# ESP32_ublox_IMU_2020-12-27_17-32-34.net
KiCad netlist of a schematic drawn in Altium Designer
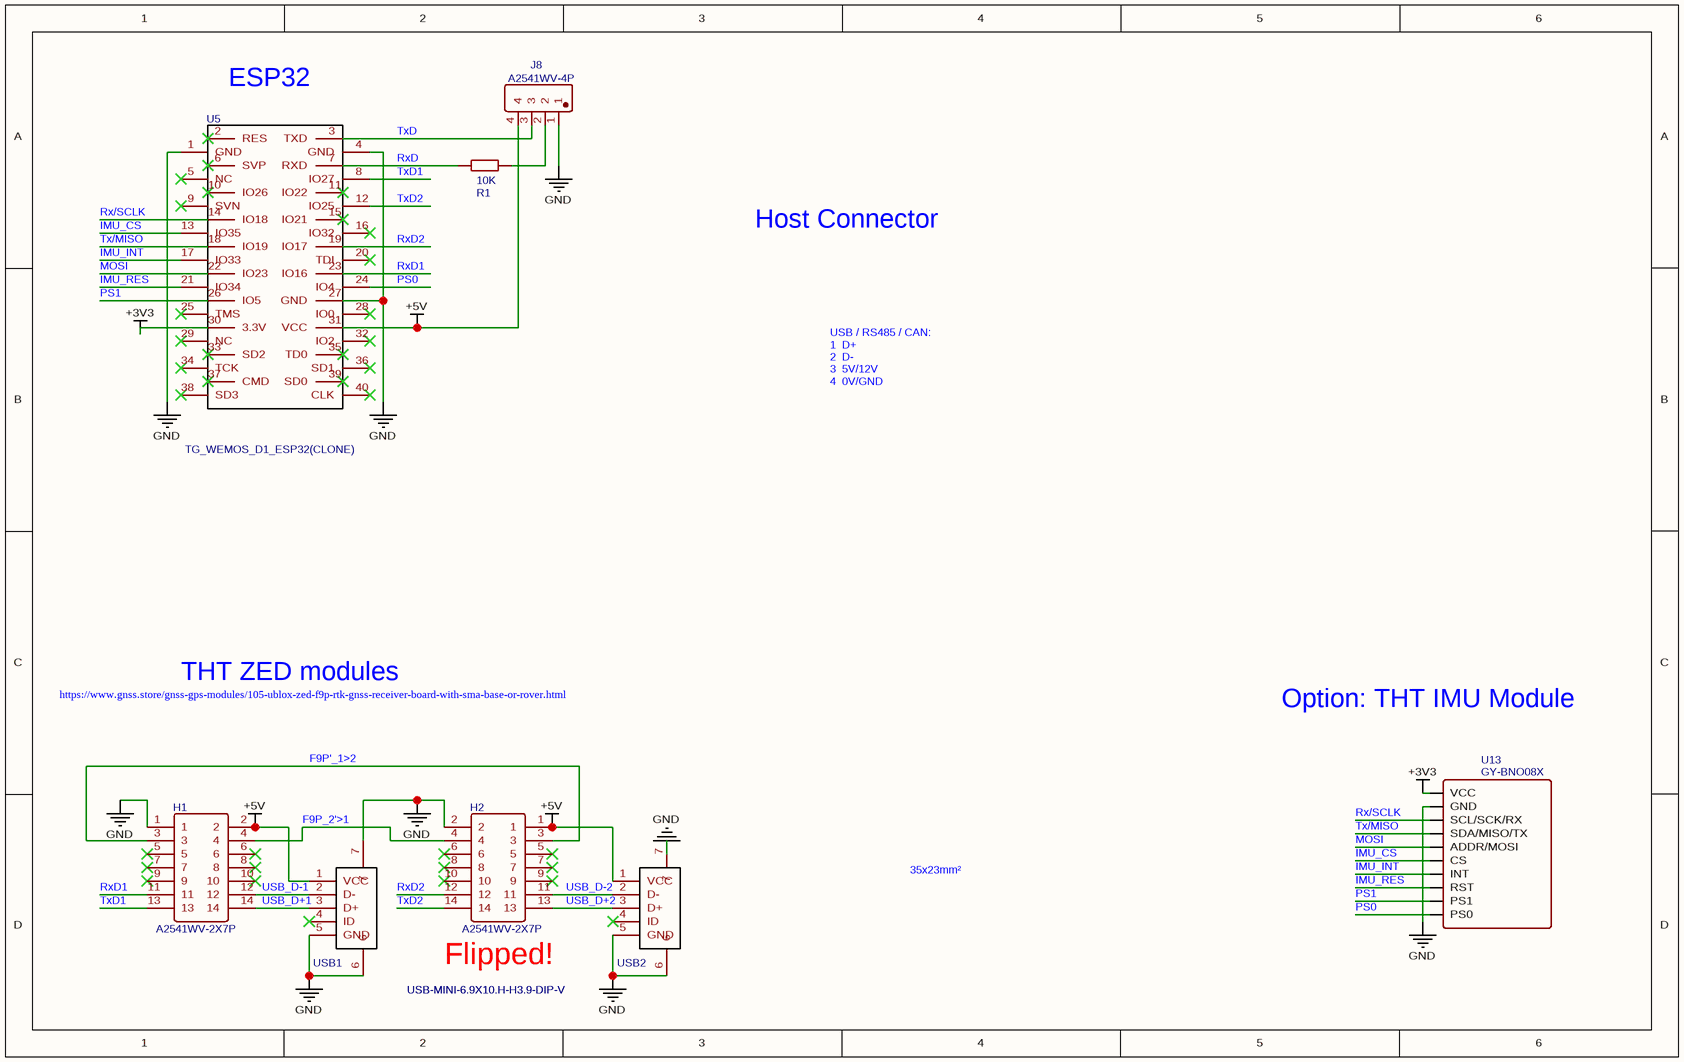
[diagram p0: ESP32 ublox IMU_2020-12-27_17-32-34.schdoc]

(export (version "E")
  (design (tool "Eeschema 10.0.6"))
  (components
    (comp (ref "H1")
      (value "A2541WV-2X7P")
      (fields
        (field (name "BOM_SUPPLIER PART") "C225522")
        (field (name "BOM_MANUFACTURER PART") "A2541WV-2x7P")
        (field (name "CONTRIBUTOR") "LCSC")
      )
      (libsource (lib "altium-import") (part "root_0_A2541WV-2X7P_"))
    )
    (comp (ref "H2")
      (value "A2541WV-2X7P")
      (fields
        (field (name "BOM_SUPPLIER PART") "C225522")
        (field (name "BOM_MANUFACTURER PART") "A2541WV-2x7P")
        (field (name "CONTRIBUTOR") "LCSC")
      )
      (libsource (lib "") (part "root_0_A2541WV-2X7P__1"))
    )
    (comp (ref "J8")
      (value "A2541WV-4P")
      (fields (field (name "BOM_SUPPLIER PART") "C225479") (field (name "CONTRIBUTOR") "LCSC"))
      (libsource (lib "altium-import") (part "root_0_A2541WV-4P_"))
    )
    (comp (ref "R1")
      (value "10K")
      (fields
        (field (name "BOM_SUPPLIER PART") "C274420")
        (field (name "BOM_MANUFACTURER PART") "RNU18F1002A520NH")
        (field (name "CONTRIBUTOR") "LCSC")
      )
      (libsource (lib "altium-import") (part "root_0_10K_"))
    )
    (comp (ref "U5")
      (value "TG_WEMOS_D1_ESP32(CLONE)")
      (fields
        (field (name "BOM_MANUFACTURER PART") "New SchematicLib")
        (field (name "BOM_SUPPLIER PART") "undefined")
        (field (name "CONTRIBUTOR") "John Archbold")
      )
      (libsource (lib "altium-import") (part "root_0_TG_WEMOS_D1_ESP32(CLONE)_"))
    )
    (comp (ref "U13")
      (value "GY-BNO08X")
      (fields (field (name "CONTRIBUTOR") "t107408038"))
      (libsource (lib "altium-import") (part "root_0_GY-BNO08X_"))
    )
    (comp (ref "USB1")
      (value "USB-MINI-6.9X10.H-H3.9-DIP-V")
      (fields (field (name "BOM_SUPPLIER PART") "C13453") (field (name "CONTRIBUTOR") "LCSC"))
      (libsource (lib "altium-import") (part "root_3_USB-MINI-6.9X10.H-H3.9-DIP-V_"))
    )
    (comp (ref "USB2")
      (value "USB-MINI-6.9X10.H-H3.9-DIP-V")
      (fields (field (name "BOM_SUPPLIER PART") "C13453") (field (name "CONTRIBUTOR") "LCSC"))
      (libsource (lib "altium-import") (part "root_3_USB-MINI-6.9X10.H-H3.9-DIP-V_"))
    )
  )
  (nets
    (net (code "1") (name "+3V3") (class "Default")
      (node (ref "U13") (pin "1") (pinfunction "VCC_1") (pintype "passive"))
      (node (ref "U5") (pin "30") (pinfunction "3.3V_30") (pintype "passive"))
    )
    (net (code "2") (name "+5V") (class "Default")
      (node (ref "H1") (pin "2") (pinfunction "2_2") (pintype "passive"))
      (node (ref "H2") (pin "1") (pinfunction "1_1") (pintype "passive"))
      (node (ref "J8") (pin "4") (pinfunction "4_4") (pintype "passive"))
      (node (ref "U5") (pin "31") (pinfunction "VCC_31") (pintype "passive"))
      (node (ref "USB1") (pin "1") (pinfunction "VCC_1") (pintype "passive"))
      (node (ref "USB2") (pin "1") (pinfunction "VCC_1") (pintype "passive"))
    )
    (net (code "3") (name "/F9P'_1>2") (class "Default")
      (node (ref "H1") (pin "3") (pinfunction "3_3") (pintype "passive"))
      (node (ref "H2") (pin "3") (pinfunction "3_3") (pintype "passive"))
    )
    (net (code "4") (name "/F9P_2'>1") (class "Default")
      (node (ref "H1") (pin "4") (pinfunction "4_4") (pintype "passive"))
      (node (ref "H2") (pin "4") (pinfunction "4_4") (pintype "passive"))
    )
    (net (code "5") (name "/IMU_CS") (class "Default")
      (node (ref "U13") (pin "6") (pinfunction "CS_6") (pintype "passive"))
      (node (ref "U5") (pin "13") (pinfunction "IO35_13") (pintype "passive"))
    )
    (net (code "6") (name "/IMU_INT") (class "Default")
      (node (ref "U13") (pin "7") (pinfunction "INT_7") (pintype "passive"))
      (node (ref "U5") (pin "17") (pinfunction "IO33_17") (pintype "passive"))
    )
    (net (code "7") (name "/IMU_RES") (class "Default")
      (node (ref "U13") (pin "8") (pinfunction "RST_8") (pintype "passive"))
      (node (ref "U5") (pin "21") (pinfunction "IO34_21") (pintype "passive"))
    )
    (net (code "8") (name "/MOSI") (class "Default")
      (node (ref "U13") (pin "5") (pinfunction "ADDR/MOSI_5") (pintype "passive"))
      (node (ref "U5") (pin "22") (pinfunction "IO23_22") (pintype "passive"))
    )
    (net (code "9") (name "/PS0") (class "Default")
      (node (ref "U13") (pin "10") (pinfunction "PS0_10") (pintype "passive"))
      (node (ref "U5") (pin "24") (pinfunction "IO4_24") (pintype "passive"))
    )
    (net (code "10") (name "/PS1") (class "Default")
      (node (ref "U13") (pin "9") (pinfunction "PS1_9") (pintype "passive"))
      (node (ref "U5") (pin "26") (pinfunction "IO5_26") (pintype "passive"))
    )
    (net (code "11") (name "/RxD") (class "Default")
      (node (ref "R1") (pin "1") (pinfunction "1_1") (pintype "passive"))
      (node (ref "U5") (pin "7") (pinfunction "RXD_7") (pintype "passive"))
    )
    (net (code "12") (name "/RxD1") (class "Default")
      (node (ref "H1") (pin "11") (pinfunction "11_11") (pintype "passive"))
      (node (ref "U5") (pin "23") (pinfunction "IO16_23") (pintype "passive"))
    )
    (net (code "13") (name "/RxD2") (class "Default")
      (node (ref "H2") (pin "12") (pinfunction "12_12") (pintype "passive"))
      (node (ref "U5") (pin "19") (pinfunction "IO17_19") (pintype "passive"))
    )
    (net (code "14") (name "/Rx{slash}SCLK") (class "Default")
      (node (ref "U13") (pin "3") (pinfunction "SCL/SCK/RX_3") (pintype "passive"))
      (node (ref "U5") (pin "14") (pinfunction "IO18_14") (pintype "passive"))
    )
    (net (code "15") (name "/TxD") (class "Default")
      (node (ref "J8") (pin "3") (pinfunction "3_3") (pintype "passive"))
      (node (ref "U5") (pin "3") (pinfunction "TXD_3") (pintype "passive"))
    )
    (net (code "16") (name "/TxD1") (class "Default")
      (node (ref "H1") (pin "13") (pinfunction "13_13") (pintype "passive"))
      (node (ref "U5") (pin "8") (pinfunction "IO27_8") (pintype "passive"))
    )
    (net (code "17") (name "/TxD2") (class "Default")
      (node (ref "H2") (pin "14") (pinfunction "14_14") (pintype "passive"))
      (node (ref "U5") (pin "12") (pinfunction "IO25_12") (pintype "passive"))
    )
    (net (code "18") (name "/Tx{slash}MISO") (class "Default")
      (node (ref "U13") (pin "4") (pinfunction "SDA/MISO/TX_4") (pintype "passive"))
      (node (ref "U5") (pin "18") (pinfunction "IO19_18") (pintype "passive"))
    )
    (net (code "19") (name "/USB_D+1") (class "Default")
      (node (ref "H1") (pin "14") (pinfunction "14_14") (pintype "passive"))
      (node (ref "USB1") (pin "3") (pinfunction "D+_3") (pintype "passive"))
    )
    (net (code "20") (name "/USB_D+2") (class "Default")
      (node (ref "H2") (pin "13") (pinfunction "13_13") (pintype "passive"))
      (node (ref "USB2") (pin "3") (pinfunction "D+_3") (pintype "passive"))
    )
    (net (code "21") (name "/USB_D-1") (class "Default")
      (node (ref "H1") (pin "12") (pinfunction "12_12") (pintype "passive"))
      (node (ref "USB1") (pin "2") (pinfunction "D-_2") (pintype "passive"))
    )
    (net (code "22") (name "/USB_D-2") (class "Default")
      (node (ref "H2") (pin "11") (pinfunction "11_11") (pintype "passive"))
      (node (ref "USB2") (pin "2") (pinfunction "D-_2") (pintype "passive"))
    )
    (net (code "23") (name "GND") (class "Default")
      (node (ref "H1") (pin "1") (pinfunction "1_1") (pintype "passive"))
      (node (ref "H2") (pin "2") (pinfunction "2_2") (pintype "passive"))
      (node (ref "J8") (pin "1") (pinfunction "1_1") (pintype "passive"))
      (node (ref "U13") (pin "2") (pinfunction "GND_2") (pintype "passive"))
      (node (ref "U5") (pin "1") (pinfunction "GND_1") (pintype "passive"))
      (node (ref "U5") (pin "27") (pinfunction "GND_27") (pintype "passive"))
      (node (ref "U5") (pin "4") (pinfunction "GND_4") (pintype "passive"))
      (node (ref "USB1") (pin "5") (pinfunction "GND_5") (pintype "passive"))
      (node (ref "USB1") (pin "6") (pinfunction "6_6") (pintype "passive"))
      (node (ref "USB1") (pin "7") (pinfunction "7_7") (pintype "passive"))
      (node (ref "USB2") (pin "5") (pinfunction "GND_5") (pintype "passive"))
      (node (ref "USB2") (pin "6") (pinfunction "6_6") (pintype "passive"))
      (node (ref "USB2") (pin "7") (pinfunction "7_7") (pintype "passive"))
    )
    (net (code "24") (name "Net-(J8-Pad2)") (class "Default")
      (node (ref "J8") (pin "2") (pinfunction "2_2") (pintype "passive"))
      (node (ref "R1") (pin "2") (pinfunction "2_2") (pintype "passive"))
    )
    (net (code "25") (name "unconnected-(H1-Pad5)") (class "Default")
      (node (ref "H1") (pin "5") (pinfunction "5_5") (pintype "passive+no_connect"))
    )
    (net (code "26") (name "unconnected-(H1-Pad6)") (class "Default")
      (node (ref "H1") (pin "6") (pinfunction "6_6") (pintype "passive+no_connect"))
    )
    (net (code "27") (name "unconnected-(H1-Pad7)") (class "Default")
      (node (ref "H1") (pin "7") (pinfunction "7_7") (pintype "passive+no_connect"))
    )
    (net (code "28") (name "unconnected-(H1-Pad8)") (class "Default")
      (node (ref "H1") (pin "8") (pinfunction "8_8") (pintype "passive+no_connect"))
    )
    (net (code "29") (name "unconnected-(H1-Pad9)") (class "Default")
      (node (ref "H1") (pin "9") (pinfunction "9_9") (pintype "passive+no_connect"))
    )
    (net (code "30") (name "unconnected-(H1-Pad10)") (class "Default")
      (node (ref "H1") (pin "10") (pinfunction "10_10") (pintype "passive+no_connect"))
    )
    (net (code "31") (name "unconnected-(H2-Pad5)") (class "Default")
      (node (ref "H2") (pin "5") (pinfunction "5_5") (pintype "passive+no_connect"))
    )
    (net (code "32") (name "unconnected-(H2-Pad6)") (class "Default")
      (node (ref "H2") (pin "6") (pinfunction "6_6") (pintype "passive+no_connect"))
    )
    (net (code "33") (name "unconnected-(H2-Pad7)") (class "Default")
      (node (ref "H2") (pin "7") (pinfunction "7_7") (pintype "passive+no_connect"))
    )
    (net (code "34") (name "unconnected-(H2-Pad8)") (class "Default")
      (node (ref "H2") (pin "8") (pinfunction "8_8") (pintype "passive+no_connect"))
    )
    (net (code "35") (name "unconnected-(H2-Pad9)") (class "Default")
      (node (ref "H2") (pin "9") (pinfunction "9_9") (pintype "passive+no_connect"))
    )
    (net (code "36") (name "unconnected-(H2-Pad10)") (class "Default")
      (node (ref "H2") (pin "10") (pinfunction "10_10") (pintype "passive+no_connect"))
    )
    (net (code "37") (name "unconnected-(U5-CLK-Pad40)") (class "Default")
      (node (ref "U5") (pin "40") (pinfunction "CLK_40") (pintype "passive+no_connect"))
    )
    (net (code "38") (name "unconnected-(U5-CMD-Pad37)") (class "Default")
      (node (ref "U5") (pin "37") (pinfunction "CMD_37") (pintype "passive+no_connect"))
    )
    (net (code "39") (name "unconnected-(U5-IO0-Pad28)") (class "Default")
      (node (ref "U5") (pin "28") (pinfunction "IO0_28") (pintype "passive+no_connect"))
    )
    (net (code "40") (name "unconnected-(U5-IO2-Pad32)") (class "Default")
      (node (ref "U5") (pin "32") (pinfunction "IO2_32") (pintype "passive+no_connect"))
    )
    (net (code "41") (name "unconnected-(U5-IO21-Pad15)") (class "Default")
      (node (ref "U5") (pin "15") (pinfunction "IO21_15") (pintype "passive+no_connect"))
    )
    (net (code "42") (name "unconnected-(U5-IO22-Pad11)") (class "Default")
      (node (ref "U5") (pin "11") (pinfunction "IO22_11") (pintype "passive+no_connect"))
    )
    (net (code "43") (name "unconnected-(U5-IO26-Pad10)") (class "Default")
      (node (ref "U5") (pin "10") (pinfunction "IO26_10") (pintype "passive+no_connect"))
    )
    (net (code "44") (name "unconnected-(U5-IO32-Pad16)") (class "Default")
      (node (ref "U5") (pin "16") (pinfunction "IO32_16") (pintype "passive+no_connect"))
    )
    (net (code "45") (name "unconnected-(U5-NC-Pad5)") (class "Default")
      (node (ref "U5") (pin "5") (pinfunction "NC_5") (pintype "passive+no_connect"))
    )
    (net (code "46") (name "unconnected-(U5-NC-Pad29)") (class "Default")
      (node (ref "U5") (pin "29") (pinfunction "NC_29") (pintype "passive+no_connect"))
    )
    (net (code "47") (name "unconnected-(U5-RES-Pad2)") (class "Default")
      (node (ref "U5") (pin "2") (pinfunction "RES_2") (pintype "passive+no_connect"))
    )
    (net (code "48") (name "unconnected-(U5-SD0-Pad39)") (class "Default")
      (node (ref "U5") (pin "39") (pinfunction "SD0_39") (pintype "passive+no_connect"))
    )
    (net (code "49") (name "unconnected-(U5-SD1-Pad36)") (class "Default")
      (node (ref "U5") (pin "36") (pinfunction "SD1_36") (pintype "passive+no_connect"))
    )
    (net (code "50") (name "unconnected-(U5-SD2-Pad33)") (class "Default")
      (node (ref "U5") (pin "33") (pinfunction "SD2_33") (pintype "passive+no_connect"))
    )
    (net (code "51") (name "unconnected-(U5-SD3-Pad38)") (class "Default")
      (node (ref "U5") (pin "38") (pinfunction "SD3_38") (pintype "passive+no_connect"))
    )
    (net (code "52") (name "unconnected-(U5-SVN-Pad9)") (class "Default")
      (node (ref "U5") (pin "9") (pinfunction "SVN_9") (pintype "passive+no_connect"))
    )
    (net (code "53") (name "unconnected-(U5-SVP-Pad6)") (class "Default")
      (node (ref "U5") (pin "6") (pinfunction "SVP_6") (pintype "passive+no_connect"))
    )
    (net (code "54") (name "unconnected-(U5-TCK-Pad34)") (class "Default")
      (node (ref "U5") (pin "34") (pinfunction "TCK_34") (pintype "passive+no_connect"))
    )
    (net (code "55") (name "unconnected-(U5-TD0-Pad35)") (class "Default")
      (node (ref "U5") (pin "35") (pinfunction "TD0_35") (pintype "passive+no_connect"))
    )
    (net (code "56") (name "unconnected-(U5-TDI-Pad20)") (class "Default")
      (node (ref "U5") (pin "20") (pinfunction "TDI_20") (pintype "passive+no_connect"))
    )
    (net (code "57") (name "unconnected-(U5-TMS-Pad25)") (class "Default")
      (node (ref "U5") (pin "25") (pinfunction "TMS_25") (pintype "passive+no_connect"))
    )
    (net (code "58") (name "unconnected-(USB1-ID-Pad4)") (class "Default")
      (node (ref "USB1") (pin "4") (pinfunction "ID_4") (pintype "passive+no_connect"))
    )
    (net (code "59") (name "unconnected-(USB2-ID-Pad4)") (class "Default")
      (node (ref "USB2") (pin "4") (pinfunction "ID_4") (pintype "passive+no_connect"))
    )
  )
)
